# mcu_gateway.net
KiCad netlist of a schematic drawn in Altium Designer
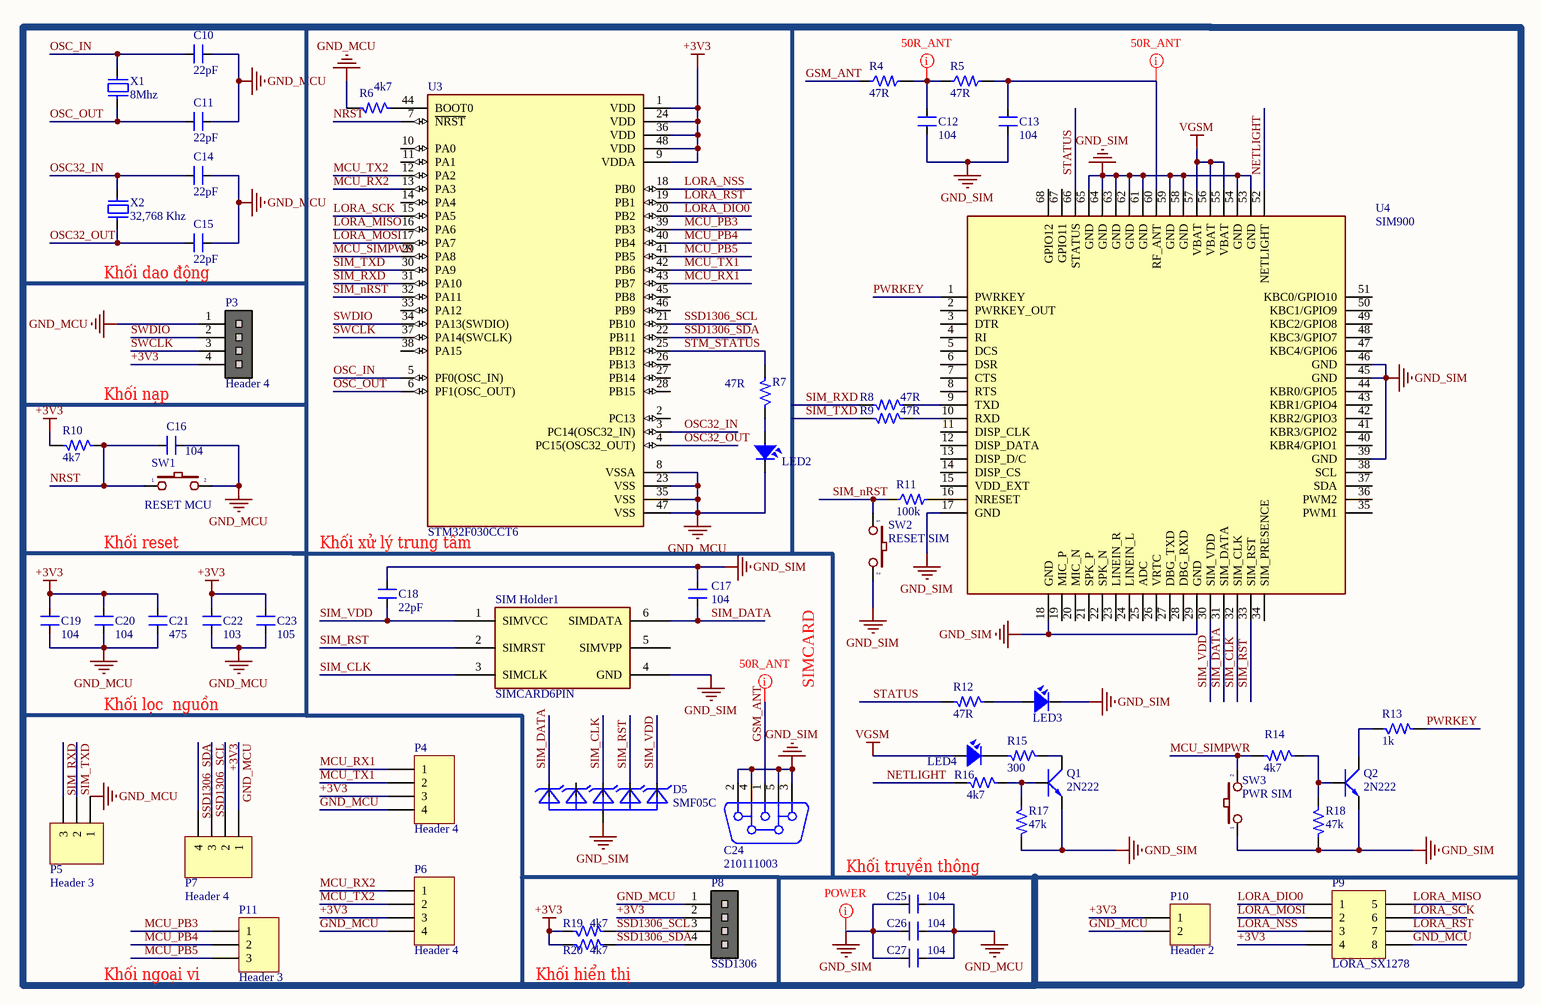
[diagram p0: mcu_gateway.SchDoc]

(export (version "E")
  (design (tool "Eeschema 10.0.6"))
  (components
    (comp (ref "C10")
      (value "22pF")
      (footprint "SM-0805")
      (description "Cap SMD")
      (libsource (lib "syhaunguyen") (part "CM"))
    )
    (comp (ref "C11")
      (value "22pF")
      (footprint "SM-0805")
      (description "Cap SMD")
      (libsource (lib "syhaunguyen") (part "CM"))
    )
    (comp (ref "C12")
      (value "104")
      (footprint "SM-0805")
      (description "Cap SMD")
      (libsource (lib "syhaunguyen") (part "CM"))
    )
    (comp (ref "C13")
      (value "104")
      (footprint "SM-0805")
      (description "Cap SMD")
      (libsource (lib "syhaunguyen") (part "CM"))
    )
    (comp (ref "C14")
      (value "22pF")
      (footprint "SM-0805")
      (description "Cap SMD")
      (libsource (lib "syhaunguyen") (part "CM"))
    )
    (comp (ref "C15")
      (value "22pF")
      (footprint "SM-0805")
      (description "Cap SMD")
      (libsource (lib "syhaunguyen") (part "CM"))
    )
    (comp (ref "C16")
      (value "104")
      (footprint "SM-0805")
      (description "Cap SMD")
      (libsource (lib "syhaunguyen") (part "CM"))
    )
    (comp (ref "C17")
      (value "104")
      (footprint "SM-0805")
      (description "Cap SMD")
      (libsource (lib "syhaunguyen") (part "CM"))
    )
    (comp (ref "C18")
      (value "22pF")
      (footprint "SM-0805")
      (description "Cap SMD")
      (libsource (lib "syhaunguyen") (part "CM"))
    )
    (comp (ref "C19")
      (value "104")
      (footprint "SM-0805")
      (description "Cap SMD")
      (libsource (lib "syhaunguyen") (part "CM"))
    )
    (comp (ref "C20")
      (value "104")
      (footprint "SM-0805")
      (description "Cap SMD")
      (libsource (lib "syhaunguyen") (part "CM"))
    )
    (comp (ref "C21")
      (value "475")
      (footprint "SM-0805")
      (description "Cap SMD")
      (libsource (lib "syhaunguyen") (part "CM"))
    )
    (comp (ref "C22")
      (value "103")
      (footprint "SM-0805")
      (description "Cap SMD")
      (libsource (lib "syhaunguyen") (part "CM"))
    )
    (comp (ref "C23")
      (value "105")
      (footprint "SM-0805")
      (description "Cap SMD")
      (libsource (lib "syhaunguyen") (part "CM"))
    )
    (comp (ref "C24")
      (value "210111003")
      (footprint "SMA-RA")
      (description "CONNECTOR ANTEN")
      (fields
        (field (name "MANUFACTURER") "Würth Elektronik eiSos GmbH")
        (field (name "CREATED BY") "Christin Zierenner")
      )
      (libsource (lib "TechMT.VN_Lib_Project v2") (part "CON Ant"))
    )
    (comp (ref "C25")
      (value "104")
      (footprint "SM-0805")
      (description "Cap SMD")
      (libsource (lib "syhaunguyen") (part "CM"))
    )
    (comp (ref "C26")
      (value "104")
      (footprint "SM-0805")
      (description "Cap SMD")
      (libsource (lib "syhaunguyen") (part "CM"))
    )
    (comp (ref "C27")
      (value "104")
      (footprint "SM-0805")
      (description "Cap SMD")
      (libsource (lib "syhaunguyen") (part "CM"))
    )
    (comp (ref "D5")
      (value "SMF05C")
      (footprint "SC70-6")
      (description "12.5V Clamp 8A _8/20Âµs_ Ipp Tvs Diode Surface Mount SC-88/SC70-6/SOT-363")
      (fields (field (name "MF") "ON Semiconductor"))
      (libsource (lib "SMF05C") (part "SMF05C"))
    )
    (comp (ref "LED2")
      (value "LED")
      (footprint "LED-0805-Green")
      (libsource (lib "TechMT.VN_Lib_Project v2") (part "LED SMD"))
    )
    (comp (ref "LED3")
      (value "LED")
      (footprint "LED-0805-Green")
      (libsource (lib "TechMT.VN_Lib_Project v2") (part "LED SMD"))
    )
    (comp (ref "LED4")
      (value "LED")
      (footprint "LED-0805-Green")
      (libsource (lib "TechMT.VN_Lib_Project v2") (part "LED SMD"))
    )
    (comp (ref "P3")
      (value "Header 4")
      (footprint "HDR 1X4")
      (description "Header, 4-Pin")
      (libsource (lib "Ayric connectors") (part "Header 4"))
    )
    (comp (ref "P4")
      (value "Header 4")
      (footprint "HDR1X4")
      (description "Header, 4-Pin")
      (fields (field (name "PUBLISHER") "Altium Limited"))
      (libsource (lib "") (part "Header 4_1"))
    )
    (comp (ref "P5")
      (value "Header 3")
      (footprint "HDR1X3")
      (description "Header, 3-Pin")
      (fields (field (name "PUBLISHER") "Altium Limited"))
      (libsource (lib "Library AL") (part "Header 3"))
    )
    (comp (ref "P6")
      (value "Header 4")
      (footprint "HDR1X4")
      (description "Header, 4-Pin")
      (fields (field (name "PUBLISHER") "Altium Limited"))
      (libsource (lib "") (part "Header 4_1"))
    )
    (comp (ref "P7")
      (value "Header 4")
      (footprint "HDR1X4")
      (description "Header, 4-Pin")
      (fields (field (name "PUBLISHER") "Altium Limited"))
      (libsource (lib "Library AL") (part "Header 4"))
    )
    (comp (ref "P8")
      (value "SSD1306")
      (footprint "HDR 1X4")
      (description "Header, 4-Pin")
      (libsource (lib "Ayric connectors") (part "Header 4"))
    )
    (comp (ref "P9")
      (value "LORA_SX1278")
      (footprint "HDR2X4_CEN")
      (description "Header, 4-Pin, Dual row")
      (fields (field (name "PUBLISHER") "Altium Limited"))
      (libsource (lib "Library AL") (part "Header 4X2A"))
    )
    (comp (ref "P10")
      (value "Header 2")
      (footprint "HDR1X2")
      (description "Header, 2-Pin")
      (fields (field (name "PUBLISHER") "Altium Limited"))
      (libsource (lib "Library AL") (part "Header 2"))
    )
    (comp (ref "P11")
      (value "Header 3")
      (footprint "HDR1X3")
      (description "Header, 3-Pin")
      (fields (field (name "PUBLISHER") "Altium Limited"))
      (libsource (lib "") (part "Header 3_1"))
    )
    (comp (ref "Q1")
      (value "2N222")
      (footprint "TO92-123")
      (description "NPN 600mW, ECB")
      (fields (field (name "CREAT BY") "MT-TECH.VN"))
      (libsource (lib "TechMT.VN_Lib_Project v2") (part "2N222"))
    )
    (comp (ref "Q2")
      (value "2N222")
      (footprint "TO92-123")
      (description "NPN 600mW, ECB")
      (fields (field (name "CREAT BY") "MT-TECH.VN"))
      (libsource (lib "TechMT.VN_Lib_Project v2") (part "2N222"))
    )
    (comp (ref "R4")
      (value "47R")
      (footprint "R-0805")
      (description "dien tro")
      (libsource (lib "oggy") (part "resistor"))
    )
    (comp (ref "R5")
      (value "47R")
      (footprint "R-0805")
      (description "dien tro")
      (libsource (lib "oggy") (part "resistor"))
    )
    (comp (ref "R6")
      (value "4k7")
      (footprint "R-0805")
      (description "dien tro")
      (libsource (lib "oggy") (part "resistor"))
    )
    (comp (ref "R7")
      (value "47R")
      (footprint "R-0805")
      (description "dien tro")
      (libsource (lib "oggy") (part "resistor"))
    )
    (comp (ref "R8")
      (value "47R")
      (footprint "R-0805")
      (description "dien tro")
      (libsource (lib "oggy") (part "resistor"))
    )
    (comp (ref "R9")
      (value "47R")
      (footprint "R-0805")
      (description "dien tro")
      (libsource (lib "oggy") (part "resistor"))
    )
    (comp (ref "R10")
      (value "4k7")
      (footprint "R-0805")
      (description "dien tro")
      (libsource (lib "oggy") (part "resistor"))
    )
    (comp (ref "R11")
      (value "100k")
      (footprint "R-0805")
      (description "dien tro")
      (libsource (lib "oggy") (part "resistor"))
    )
    (comp (ref "R12")
      (value "47R")
      (footprint "R-0805")
      (description "dien tro")
      (libsource (lib "oggy") (part "resistor"))
    )
    (comp (ref "R13")
      (value "1k")
      (footprint "R-0805")
      (description "dien tro")
      (libsource (lib "oggy") (part "resistor"))
    )
    (comp (ref "R14")
      (value "4k7")
      (footprint "R-0805")
      (description "dien tro")
      (libsource (lib "oggy") (part "resistor"))
    )
    (comp (ref "R15")
      (value "300")
      (footprint "R-0805")
      (description "dien tro")
      (libsource (lib "oggy") (part "resistor"))
    )
    (comp (ref "R16")
      (value "4k7")
      (footprint "R-0805")
      (description "dien tro")
      (libsource (lib "oggy") (part "resistor"))
    )
    (comp (ref "R17")
      (value "47k")
      (footprint "R-0805")
      (description "dien tro")
      (libsource (lib "oggy") (part "resistor"))
    )
    (comp (ref "R18")
      (value "47k")
      (footprint "R-0805")
      (description "dien tro")
      (libsource (lib "oggy") (part "resistor"))
    )
    (comp (ref "R19")
      (value "4k7")
      (footprint "R-0805")
      (description "dien tro")
      (libsource (lib "oggy") (part "resistor"))
    )
    (comp (ref "R20")
      (value "4k7")
      (footprint "R-0805")
      (description "dien tro")
      (libsource (lib "oggy") (part "resistor"))
    )
    (comp (ref "SIM Holder1")
      (value "SIMCARD6PIN")
      (footprint "SIMCARD6pin")
      (libsource (lib "AYRIC Library") (part "SIMCARD6PIN"))
    )
    (comp (ref "SW1")
      (value "RESET MCU")
      (footprint "SW1-SMD")
      (description "Switch button 2 pin")
      (libsource (lib "TechMT.VN_Lib_Project v2") (part "SW2"))
    )
    (comp (ref "SW2")
      (value "RESET SIM")
      (footprint "SW1-SMD")
      (description "Switch button 2 pin")
      (libsource (lib "TechMT.VN_Lib_Project v2") (part "SW2"))
    )
    (comp (ref "SW3")
      (value "PWR SIM")
      (footprint "SW1-SMD")
      (description "Switch button 2 pin")
      (libsource (lib "TechMT.VN_Lib_Project v2") (part "SW2"))
    )
    (comp (ref "U3")
      (value "STM32F030CCT6")
      (footprint "QFP50P900X900X160-48N")
      (description "ARMÂ® CortexÂ®-M0 STM32F0 Microcontroller IC 32-Bit 48MHz 256KB _256K x 8_ FLASH 48-LQFP _7x7_")
      (fields (field (name "MF") "STMicroelectronics") (field (name "DIGI-KEY_PART_NUMBER") "497-17332-2-ND"))
      (libsource (lib "STM32F030CCT6") (part "STM32F030CCT6"))
    )
    (comp (ref "U4") (value "SIM900") (footprint "SIM900") (libsource (lib "AYRIC Library") (part "SIM900")))
    (comp (ref "X1")
      (value "8Mhz")
      (footprint "XT2")
      (description "Crystal For all Crystal 2pin.")
      (libsource (lib "syhaunguyen") (part "XT2"))
    )
    (comp (ref "X2")
      (value "32,768 Khz")
      (footprint "XT32k")
      (description "Crystal 32,768kHz for timer real")
      (libsource (lib "syhaunguyen") (part "XT32k"))
    )
  )
  (nets
    (net (code "1") (name "+3V3") (class "Default")
      (node (ref "C19") (pin "2") (pinfunction "2_2") (pintype "passive"))
      (node (ref "C20") (pin "2") (pinfunction "2_2") (pintype "passive"))
      (node (ref "C21") (pin "2") (pinfunction "2_2") (pintype "passive"))
      (node (ref "C22") (pin "2") (pinfunction "2_2") (pintype "passive"))
      (node (ref "C23") (pin "2") (pinfunction "2_2") (pintype "passive"))
      (node (ref "P10") (pin "1") (pinfunction "1_1") (pintype "passive"))
      (node (ref "P3") (pin "4") (pinfunction "4_4") (pintype "passive"))
      (node (ref "P4") (pin "3") (pinfunction "3_3") (pintype "passive"))
      (node (ref "P6") (pin "3") (pinfunction "3_3") (pintype "passive"))
      (node (ref "P7") (pin "2") (pinfunction "2_2") (pintype "passive"))
      (node (ref "P8") (pin "2") (pinfunction "2_2") (pintype "passive"))
      (node (ref "P9") (pin "4") (pinfunction "4_4") (pintype "passive"))
      (node (ref "R10") (pin "2") (pinfunction "2_2") (pintype "passive"))
      (node (ref "R19") (pin "1") (pinfunction "1_1") (pintype "passive"))
      (node (ref "R20") (pin "1") (pinfunction "1_1") (pintype "passive"))
      (node (ref "U3") (pin "1") (pinfunction "VDD_1") (pintype "power_in"))
      (node (ref "U3") (pin "24") (pinfunction "VDD_24") (pintype "power_in"))
      (node (ref "U3") (pin "36") (pinfunction "VDD_36") (pintype "power_in"))
      (node (ref "U3") (pin "48") (pinfunction "VDD_48") (pintype "power_in"))
      (node (ref "U3") (pin "9") (pinfunction "VDDA_9") (pintype "power_in"))
    )
    (net (code "2") (name "/GSM_ANT") (class "Default")
      (node (ref "C24") (pin "1") (pinfunction "1_1") (pintype "passive"))
      (node (ref "R4") (pin "1") (pinfunction "1_1") (pintype "passive"))
    )
    (net (code "3") (name "/LORA_DIO0") (class "Default")
      (node (ref "P9") (pin "1") (pinfunction "1_1") (pintype "passive"))
      (node (ref "U3") (pin "20") (pinfunction "PB2_20") (pintype "bidirectional"))
    )
    (net (code "4") (name "/LORA_MISO") (class "Default")
      (node (ref "P9") (pin "5") (pinfunction "5_5") (pintype "passive"))
      (node (ref "U3") (pin "16") (pinfunction "PA6_16") (pintype "bidirectional"))
    )
    (net (code "5") (name "/LORA_MOSI") (class "Default")
      (node (ref "P9") (pin "2") (pinfunction "2_2") (pintype "passive"))
      (node (ref "U3") (pin "17") (pinfunction "PA7_17") (pintype "bidirectional"))
    )
    (net (code "6") (name "/LORA_NSS") (class "Default")
      (node (ref "P9") (pin "3") (pinfunction "3_3") (pintype "passive"))
      (node (ref "U3") (pin "18") (pinfunction "PB0_18") (pintype "bidirectional"))
    )
    (net (code "7") (name "/LORA_RST") (class "Default")
      (node (ref "P9") (pin "7") (pinfunction "7_7") (pintype "passive"))
      (node (ref "U3") (pin "19") (pinfunction "PB1_19") (pintype "bidirectional"))
    )
    (net (code "8") (name "/LORA_SCK") (class "Default")
      (node (ref "P9") (pin "6") (pinfunction "6_6") (pintype "passive"))
      (node (ref "U3") (pin "15") (pinfunction "PA5_15") (pintype "bidirectional"))
    )
    (net (code "9") (name "/MCU_PB3") (class "Default")
      (node (ref "P11") (pin "1") (pinfunction "1_1") (pintype "passive"))
      (node (ref "U3") (pin "39") (pinfunction "PB3_39") (pintype "bidirectional"))
    )
    (net (code "10") (name "/MCU_PB4") (class "Default")
      (node (ref "P11") (pin "2") (pinfunction "2_2") (pintype "passive"))
      (node (ref "U3") (pin "40") (pinfunction "PB4_40") (pintype "bidirectional"))
    )
    (net (code "11") (name "/MCU_PB5") (class "Default")
      (node (ref "P11") (pin "3") (pinfunction "3_3") (pintype "passive"))
      (node (ref "U3") (pin "41") (pinfunction "PB5_41") (pintype "bidirectional"))
    )
    (net (code "12") (name "/MCU_RX1") (class "Default")
      (node (ref "P4") (pin "1") (pinfunction "1_1") (pintype "passive"))
      (node (ref "U3") (pin "43") (pinfunction "PB7_43") (pintype "bidirectional"))
    )
    (net (code "13") (name "/MCU_RX2") (class "Default")
      (node (ref "P6") (pin "1") (pinfunction "1_1") (pintype "passive"))
      (node (ref "U3") (pin "13") (pinfunction "PA3_13") (pintype "bidirectional"))
    )
    (net (code "14") (name "/MCU_SIMPWR") (class "Default")
      (node (ref "R14") (pin "2") (pinfunction "2_2") (pintype "passive"))
      (node (ref "SW3") (pin "2") (pinfunction "2_2") (pintype "passive"))
      (node (ref "U3") (pin "29") (pinfunction "PA8_29") (pintype "bidirectional"))
    )
    (net (code "15") (name "/MCU_TX1") (class "Default")
      (node (ref "P4") (pin "2") (pinfunction "2_2") (pintype "passive"))
      (node (ref "U3") (pin "42") (pinfunction "PB6_42") (pintype "bidirectional"))
    )
    (net (code "16") (name "/MCU_TX2") (class "Default")
      (node (ref "P6") (pin "2") (pinfunction "2_2") (pintype "passive"))
      (node (ref "U3") (pin "12") (pinfunction "PA2_12") (pintype "bidirectional"))
    )
    (net (code "17") (name "/NETLIGHT") (class "Default")
      (node (ref "R16") (pin "2") (pinfunction "2_2") (pintype "passive"))
      (node (ref "U4") (pin "52") (pinfunction "NETLIGHT_52") (pintype "passive"))
    )
    (net (code "18") (name "/NRST") (class "Default")
      (node (ref "C16") (pin "1") (pinfunction "1_1") (pintype "passive"))
      (node (ref "R10") (pin "1") (pinfunction "1_1") (pintype "passive"))
      (node (ref "SW1") (pin "1") (pinfunction "1_1") (pintype "passive"))
      (node (ref "U3") (pin "7") (pinfunction "~{NRST}_7") (pintype "bidirectional"))
    )
    (net (code "19") (name "/OSC32_IN") (class "Default")
      (node (ref "C14") (pin "2") (pinfunction "2_2") (pintype "passive"))
      (node (ref "U3") (pin "3") (pinfunction "PC14(OSC32_IN)_3") (pintype "bidirectional"))
      (node (ref "X2") (pin "2") (pinfunction "2_2") (pintype "passive"))
    )
    (net (code "20") (name "/OSC32_OUT") (class "Default")
      (node (ref "C15") (pin "2") (pinfunction "2_2") (pintype "passive"))
      (node (ref "U3") (pin "4") (pinfunction "PC15(OSC32_OUT)_4") (pintype "bidirectional"))
      (node (ref "X2") (pin "1") (pinfunction "1_1") (pintype "passive"))
    )
    (net (code "21") (name "/OSC_IN") (class "Default")
      (node (ref "C10") (pin "2") (pinfunction "2_2") (pintype "passive"))
      (node (ref "U3") (pin "5") (pinfunction "PF0(OSC_IN)_5") (pintype "bidirectional"))
      (node (ref "X1") (pin "2") (pinfunction "2_2") (pintype "passive"))
    )
    (net (code "22") (name "/OSC_OUT") (class "Default")
      (node (ref "C11") (pin "2") (pinfunction "2_2") (pintype "passive"))
      (node (ref "U3") (pin "6") (pinfunction "PF1(OSC_OUT)_6") (pintype "bidirectional"))
      (node (ref "X1") (pin "1") (pinfunction "1_1") (pintype "passive"))
    )
    (net (code "23") (name "/PWRKEY") (class "Default")
      (node (ref "R13") (pin "2") (pinfunction "2_2") (pintype "passive"))
      (node (ref "U4") (pin "1") (pinfunction "PWRKEY_1") (pintype "passive"))
    )
    (net (code "24") (name "/SIM_CLK") (class "Default")
      (node (ref "D5") (pin "4") (pinfunction "C3_4") (pintype "passive"))
      (node (ref "SIM Holder1") (pin "3") (pinfunction "SIMCLK_3") (pintype "passive"))
      (node (ref "U4") (pin "32") (pinfunction "SIM_CLK_32") (pintype "passive"))
    )
    (net (code "25") (name "/SIM_DATA") (class "Default")
      (node (ref "C17") (pin "1") (pinfunction "1_1") (pintype "passive"))
      (node (ref "D5") (pin "1") (pinfunction "C1_1") (pintype "passive"))
      (node (ref "SIM Holder1") (pin "6") (pinfunction "SIMDATA_6") (pintype "passive"))
      (node (ref "U4") (pin "31") (pinfunction "SIM_DATA_31") (pintype "passive"))
    )
    (net (code "26") (name "/SIM_RST") (class "Default")
      (node (ref "D5") (pin "5") (pinfunction "C4_5") (pintype "passive"))
      (node (ref "SIM Holder1") (pin "2") (pinfunction "SIMRST_2") (pintype "passive"))
      (node (ref "U4") (pin "33") (pinfunction "SIM_RST_33") (pintype "passive"))
    )
    (net (code "27") (name "/SIM_RXD") (class "Default")
      (node (ref "P5") (pin "3") (pinfunction "3_3") (pintype "passive"))
      (node (ref "R8") (pin "2") (pinfunction "2_2") (pintype "passive"))
      (node (ref "U3") (pin "31") (pinfunction "PA10_31") (pintype "bidirectional"))
    )
    (net (code "28") (name "/SIM_TXD") (class "Default")
      (node (ref "P5") (pin "2") (pinfunction "2_2") (pintype "passive"))
      (node (ref "R9") (pin "2") (pinfunction "2_2") (pintype "passive"))
      (node (ref "U3") (pin "30") (pinfunction "PA9_30") (pintype "bidirectional"))
    )
    (net (code "29") (name "/SIM_VDD") (class "Default")
      (node (ref "C18") (pin "1") (pinfunction "1_1") (pintype "passive"))
      (node (ref "D5") (pin "6") (pinfunction "C5_6") (pintype "passive"))
      (node (ref "SIM Holder1") (pin "1") (pinfunction "SIMVCC_1") (pintype "passive"))
      (node (ref "U4") (pin "30") (pinfunction "SIM_VDD_30") (pintype "passive"))
    )
    (net (code "30") (name "/SIM_nRST") (class "Default")
      (node (ref "R11") (pin "1") (pinfunction "1_1") (pintype "passive"))
      (node (ref "SW2") (pin "1") (pinfunction "1_1") (pintype "passive"))
      (node (ref "U3") (pin "32") (pinfunction "PA11_32") (pintype "bidirectional"))
    )
    (net (code "31") (name "/SSD1306_SCL") (class "Default")
      (node (ref "P7") (pin "3") (pinfunction "3_3") (pintype "passive"))
      (node (ref "P8") (pin "3") (pinfunction "3_3") (pintype "passive"))
      (node (ref "R19") (pin "2") (pinfunction "2_2") (pintype "passive"))
      (node (ref "U3") (pin "21") (pinfunction "PB10_21") (pintype "bidirectional"))
    )
    (net (code "32") (name "/SSD1306_SDA") (class "Default")
      (node (ref "P7") (pin "4") (pinfunction "4_4") (pintype "passive"))
      (node (ref "P8") (pin "4") (pinfunction "4_4") (pintype "passive"))
      (node (ref "R20") (pin "2") (pinfunction "2_2") (pintype "passive"))
      (node (ref "U3") (pin "22") (pinfunction "PB11_22") (pintype "bidirectional"))
    )
    (net (code "33") (name "/STATUS") (class "Default")
      (node (ref "R12") (pin "2") (pinfunction "2_2") (pintype "passive"))
      (node (ref "U4") (pin "66") (pinfunction "STATUS_66") (pintype "passive"))
    )
    (net (code "34") (name "/STM_STATUS") (class "Default")
      (node (ref "R7") (pin "2") (pinfunction "2_2") (pintype "passive"))
      (node (ref "U3") (pin "25") (pinfunction "PB12_25") (pintype "bidirectional"))
    )
    (net (code "35") (name "/SWCLK") (class "Default")
      (node (ref "P3") (pin "3") (pinfunction "3_3") (pintype "passive"))
      (node (ref "U3") (pin "37") (pinfunction "PA14(SWCLK)_37") (pintype "bidirectional"))
    )
    (net (code "36") (name "/SWDIO") (class "Default")
      (node (ref "P3") (pin "2") (pinfunction "2_2") (pintype "passive"))
      (node (ref "U3") (pin "34") (pinfunction "PA13(SWDIO)_34") (pintype "bidirectional"))
    )
    (net (code "37") (name "GND_MCU") (class "Default")
      (node (ref "C10") (pin "1") (pinfunction "1_1") (pintype "passive"))
      (node (ref "C11") (pin "1") (pinfunction "1_1") (pintype "passive"))
      (node (ref "C14") (pin "1") (pinfunction "1_1") (pintype "passive"))
      (node (ref "C15") (pin "1") (pinfunction "1_1") (pintype "passive"))
      (node (ref "C16") (pin "2") (pinfunction "2_2") (pintype "passive"))
      (node (ref "C19") (pin "1") (pinfunction "1_1") (pintype "passive"))
      (node (ref "C20") (pin "1") (pinfunction "1_1") (pintype "passive"))
      (node (ref "C21") (pin "1") (pinfunction "1_1") (pintype "passive"))
      (node (ref "C22") (pin "1") (pinfunction "1_1") (pintype "passive"))
      (node (ref "C23") (pin "1") (pinfunction "1_1") (pintype "passive"))
      (node (ref "C25") (pin "2") (pinfunction "2_2") (pintype "passive"))
      (node (ref "C26") (pin "2") (pinfunction "2_2") (pintype "passive"))
      (node (ref "C27") (pin "2") (pinfunction "2_2") (pintype "passive"))
      (node (ref "LED2") (pin "2") (pinfunction "2_2") (pintype "passive"))
      (node (ref "P10") (pin "2") (pinfunction "2_2") (pintype "passive"))
      (node (ref "P3") (pin "1") (pinfunction "1_1") (pintype "passive"))
      (node (ref "P4") (pin "4") (pinfunction "4_4") (pintype "passive"))
      (node (ref "P5") (pin "1") (pinfunction "1_1") (pintype "passive"))
      (node (ref "P6") (pin "4") (pinfunction "4_4") (pintype "passive"))
      (node (ref "P7") (pin "1") (pinfunction "1_1") (pintype "passive"))
      (node (ref "P8") (pin "1") (pinfunction "1_1") (pintype "passive"))
      (node (ref "P9") (pin "8") (pinfunction "8_8") (pintype "passive"))
      (node (ref "R6") (pin "2") (pinfunction "2_2") (pintype "passive"))
      (node (ref "SW1") (pin "2") (pinfunction "2_2") (pintype "passive"))
      (node (ref "U3") (pin "23") (pinfunction "VSS_23") (pintype "power_in"))
      (node (ref "U3") (pin "35") (pinfunction "VSS_35") (pintype "power_in"))
      (node (ref "U3") (pin "47") (pinfunction "VSS_47") (pintype "power_in"))
      (node (ref "U3") (pin "8") (pinfunction "VSSA_8") (pintype "power_in"))
    )
    (net (code "38") (name "GND_SIM") (class "Default")
      (node (ref "C12") (pin "1") (pinfunction "1_1") (pintype "passive"))
      (node (ref "C13") (pin "1") (pinfunction "1_1") (pintype "passive"))
      (node (ref "C17") (pin "2") (pinfunction "2_2") (pintype "passive"))
      (node (ref "C18") (pin "2") (pinfunction "2_2") (pintype "passive"))
      (node (ref "C24") (pin "2") (pinfunction "2_2") (pintype "passive"))
      (node (ref "C24") (pin "3") (pinfunction "3_3") (pintype "passive"))
      (node (ref "C24") (pin "4") (pinfunction "4_4") (pintype "passive"))
      (node (ref "C24") (pin "5") (pinfunction "5_5") (pintype "passive"))
      (node (ref "C25") (pin "1") (pinfunction "1_1") (pintype "passive"))
      (node (ref "C26") (pin "1") (pinfunction "1_1") (pintype "passive"))
      (node (ref "C27") (pin "1") (pinfunction "1_1") (pintype "passive"))
      (node (ref "D5") (pin "2") (pinfunction "A_2") (pintype "passive"))
      (node (ref "LED3") (pin "2") (pinfunction "2_2") (pintype "passive"))
      (node (ref "Q1") (pin "1") (pinfunction "E_1") (pintype "passive"))
      (node (ref "Q2") (pin "1") (pinfunction "E_1") (pintype "passive"))
      (node (ref "R17") (pin "2") (pinfunction "2_2") (pintype "passive"))
      (node (ref "R18") (pin "2") (pinfunction "2_2") (pintype "passive"))
      (node (ref "SIM Holder1") (pin "4") (pinfunction "GND_4") (pintype "passive"))
      (node (ref "SW2") (pin "2") (pinfunction "2_2") (pintype "passive"))
      (node (ref "SW3") (pin "1") (pinfunction "1_1") (pintype "passive"))
      (node (ref "U4") (pin "17") (pinfunction "GND_17") (pintype "passive"))
      (node (ref "U4") (pin "18") (pinfunction "GND_18") (pintype "passive"))
      (node (ref "U4") (pin "29") (pinfunction "GND_29") (pintype "passive"))
      (node (ref "U4") (pin "39") (pinfunction "GND_39") (pintype "passive"))
      (node (ref "U4") (pin "45") (pinfunction "GND_45") (pintype "passive"))
      (node (ref "U4") (pin "46") (pinfunction "GND_46") (pintype "passive"))
      (node (ref "U4") (pin "53") (pinfunction "GND_53") (pintype "passive"))
      (node (ref "U4") (pin "54") (pinfunction "GND_54") (pintype "passive"))
      (node (ref "U4") (pin "58") (pinfunction "GND_58") (pintype "passive"))
      (node (ref "U4") (pin "59") (pinfunction "GND_59") (pintype "passive"))
      (node (ref "U4") (pin "61") (pinfunction "GND_61") (pintype "passive"))
      (node (ref "U4") (pin "62") (pinfunction "GND_62") (pintype "passive"))
      (node (ref "U4") (pin "63") (pinfunction "GND_63") (pintype "passive"))
      (node (ref "U4") (pin "64") (pinfunction "GND_64") (pintype "passive"))
      (node (ref "U4") (pin "65") (pinfunction "GND_65") (pintype "passive"))
    )
    (net (code "39") (name "Net-(C12-Pad2)") (class "Default")
      (node (ref "C12") (pin "2") (pinfunction "2_2") (pintype "passive"))
      (node (ref "R4") (pin "2") (pinfunction "2_2") (pintype "passive"))
      (node (ref "R5") (pin "1") (pinfunction "1_1") (pintype "passive"))
    )
    (net (code "40") (name "Net-(LED2-Pad1)") (class "Default")
      (node (ref "LED2") (pin "1") (pinfunction "1_1") (pintype "passive"))
      (node (ref "R7") (pin "1") (pinfunction "1_1") (pintype "passive"))
    )
    (net (code "41") (name "Net-(LED3-Pad1)") (class "Default")
      (node (ref "LED3") (pin "1") (pinfunction "1_1") (pintype "passive"))
      (node (ref "R12") (pin "1") (pinfunction "1_1") (pintype "passive"))
    )
    (net (code "42") (name "Net-(LED4-Pad2)") (class "Default")
      (node (ref "LED4") (pin "2") (pinfunction "2_2") (pintype "passive"))
      (node (ref "R15") (pin "2") (pinfunction "2_2") (pintype "passive"))
    )
    (net (code "43") (name "Net-(Q1-B)") (class "Default")
      (node (ref "Q1") (pin "2") (pinfunction "B_2") (pintype "passive"))
      (node (ref "R16") (pin "1") (pinfunction "1_1") (pintype "passive"))
      (node (ref "R17") (pin "1") (pinfunction "1_1") (pintype "passive"))
    )
    (net (code "44") (name "Net-(Q1-C)") (class "Default")
      (node (ref "Q1") (pin "3") (pinfunction "C_3") (pintype "passive"))
      (node (ref "R15") (pin "1") (pinfunction "1_1") (pintype "passive"))
    )
    (net (code "45") (name "Net-(Q2-B)") (class "Default")
      (node (ref "Q2") (pin "2") (pinfunction "B_2") (pintype "passive"))
      (node (ref "R14") (pin "1") (pinfunction "1_1") (pintype "passive"))
      (node (ref "R18") (pin "1") (pinfunction "1_1") (pintype "passive"))
    )
    (net (code "46") (name "Net-(Q2-C)") (class "Default")
      (node (ref "Q2") (pin "3") (pinfunction "C_3") (pintype "passive"))
      (node (ref "R13") (pin "1") (pinfunction "1_1") (pintype "passive"))
    )
    (net (code "47") (name "Net-(U3-BOOT0)") (class "Default")
      (node (ref "R6") (pin "1") (pinfunction "1_1") (pintype "passive"))
      (node (ref "U3") (pin "44") (pinfunction "BOOT0_44") (pintype "passive"))
    )
    (net (code "48") (name "Net-(U4-NRESET)") (class "Default")
      (node (ref "R11") (pin "2") (pinfunction "2_2") (pintype "passive"))
      (node (ref "U4") (pin "16") (pinfunction "NRESET_16") (pintype "passive"))
    )
    (net (code "49") (name "Net-(U4-RF_ANT)") (class "Default")
      (node (ref "C13") (pin "2") (pinfunction "2_2") (pintype "passive"))
      (node (ref "R5") (pin "2") (pinfunction "2_2") (pintype "passive"))
      (node (ref "U4") (pin "60") (pinfunction "RF_ANT_60") (pintype "passive"))
    )
    (net (code "50") (name "Net-(U4-RXD)") (class "Default")
      (node (ref "R9") (pin "1") (pinfunction "1_1") (pintype "passive"))
      (node (ref "U4") (pin "10") (pinfunction "RXD_10") (pintype "passive"))
    )
    (net (code "51") (name "Net-(U4-TXD)") (class "Default")
      (node (ref "R8") (pin "1") (pinfunction "1_1") (pintype "passive"))
      (node (ref "U4") (pin "9") (pinfunction "TXD_9") (pintype "passive"))
    )
    (net (code "52") (name "VGSM") (class "Default")
      (node (ref "LED4") (pin "1") (pinfunction "1_1") (pintype "passive"))
      (node (ref "U4") (pin "55") (pinfunction "VBAT_55") (pintype "passive"))
      (node (ref "U4") (pin "56") (pinfunction "VBAT_56") (pintype "passive"))
      (node (ref "U4") (pin "57") (pinfunction "VBAT_57") (pintype "passive"))
    )
    (net (code "53") (name "unconnected-(D5-C2-Pad3)") (class "Default")
      (node (ref "D5") (pin "3") (pinfunction "C2_3") (pintype "passive"))
    )
    (net (code "54") (name "unconnected-(SIM Holder1-SIMVPP-Pad5)") (class "Default")
      (node (ref "SIM Holder1") (pin "5") (pinfunction "SIMVPP_5") (pintype "passive"))
    )
    (net (code "55") (name "unconnected-(U3-PA0-Pad10)") (class "Default")
      (node (ref "U3") (pin "10") (pinfunction "PA0_10") (pintype "bidirectional"))
    )
    (net (code "56") (name "unconnected-(U3-PA1-Pad11)") (class "Default")
      (node (ref "U3") (pin "11") (pinfunction "PA1_11") (pintype "bidirectional"))
    )
    (net (code "57") (name "unconnected-(U3-PA4-Pad14)") (class "Default")
      (node (ref "U3") (pin "14") (pinfunction "PA4_14") (pintype "bidirectional"))
    )
    (net (code "58") (name "unconnected-(U3-PA12-Pad33)") (class "Default")
      (node (ref "U3") (pin "33") (pinfunction "PA12_33") (pintype "bidirectional"))
    )
    (net (code "59") (name "unconnected-(U3-PA15-Pad38)") (class "Default")
      (node (ref "U3") (pin "38") (pinfunction "PA15_38") (pintype "bidirectional"))
    )
    (net (code "60") (name "unconnected-(U3-PB8-Pad45)") (class "Default")
      (node (ref "U3") (pin "45") (pinfunction "PB8_45") (pintype "bidirectional"))
    )
    (net (code "61") (name "unconnected-(U3-PB9-Pad46)") (class "Default")
      (node (ref "U3") (pin "46") (pinfunction "PB9_46") (pintype "bidirectional"))
    )
    (net (code "62") (name "unconnected-(U3-PB13-Pad26)") (class "Default")
      (node (ref "U3") (pin "26") (pinfunction "PB13_26") (pintype "bidirectional"))
    )
    (net (code "63") (name "unconnected-(U3-PB14-Pad27)") (class "Default")
      (node (ref "U3") (pin "27") (pinfunction "PB14_27") (pintype "bidirectional"))
    )
    (net (code "64") (name "unconnected-(U3-PB15-Pad28)") (class "Default")
      (node (ref "U3") (pin "28") (pinfunction "PB15_28") (pintype "bidirectional"))
    )
    (net (code "65") (name "unconnected-(U3-PC13-Pad2)") (class "Default")
      (node (ref "U3") (pin "2") (pinfunction "PC13_2") (pintype "bidirectional"))
    )
    (net (code "66") (name "unconnected-(U4-ADC-Pad25)") (class "Default")
      (node (ref "U4") (pin "25") (pinfunction "ADC_25") (pintype "passive"))
    )
    (net (code "67") (name "unconnected-(U4-CTS-Pad7)") (class "Default")
      (node (ref "U4") (pin "7") (pinfunction "CTS_7") (pintype "passive"))
    )
    (net (code "68") (name "unconnected-(U4-DBG_RXD-Pad28)") (class "Default")
      (node (ref "U4") (pin "28") (pinfunction "DBG_RXD_28") (pintype "passive"))
    )
    (net (code "69") (name "unconnected-(U4-DBG_TXD-Pad27)") (class "Default")
      (node (ref "U4") (pin "27") (pinfunction "DBG_TXD_27") (pintype "passive"))
    )
    (net (code "70") (name "unconnected-(U4-DCS-Pad5)") (class "Default")
      (node (ref "U4") (pin "5") (pinfunction "DCS_5") (pintype "passive"))
    )
    (net (code "71") (name "unconnected-(U4-DISP_CLK-Pad11)") (class "Default")
      (node (ref "U4") (pin "11") (pinfunction "DISP_CLK_11") (pintype "passive"))
    )
    (net (code "72") (name "unconnected-(U4-DISP_CS-Pad14)") (class "Default")
      (node (ref "U4") (pin "14") (pinfunction "DISP_CS_14") (pintype "passive"))
    )
    (net (code "73") (name "unconnected-(U4-DISP_DATA-Pad12)") (class "Default")
      (node (ref "U4") (pin "12") (pinfunction "DISP_DATA_12") (pintype "passive"))
    )
    (net (code "74") (name "unconnected-(U4-DISP_D{slash}C-Pad13)") (class "Default")
      (node (ref "U4") (pin "13") (pinfunction "DISP_D/C_13") (pintype "passive"))
    )
    (net (code "75") (name "unconnected-(U4-DSR-Pad6)") (class "Default")
      (node (ref "U4") (pin "6") (pinfunction "DSR_6") (pintype "passive"))
    )
    (net (code "76") (name "unconnected-(U4-DTR-Pad3)") (class "Default")
      (node (ref "U4") (pin "3") (pinfunction "DTR_3") (pintype "passive"))
    )
    (net (code "77") (name "unconnected-(U4-GPIO11-Pad67)") (class "Default")
      (node (ref "U4") (pin "67") (pinfunction "GPIO11_67") (pintype "passive"))
    )
    (net (code "78") (name "unconnected-(U4-GPIO12-Pad68)") (class "Default")
      (node (ref "U4") (pin "68") (pinfunction "GPIO12_68") (pintype "passive"))
    )
    (net (code "79") (name "unconnected-(U4-KBC0{slash}GPIO10-Pad51)") (class "Default")
      (node (ref "U4") (pin "51") (pinfunction "KBC0/GPIO10_51") (pintype "passive"))
    )
    (net (code "80") (name "unconnected-(U4-KBC1{slash}GPIO9-Pad50)") (class "Default")
      (node (ref "U4") (pin "50") (pinfunction "KBC1/GPIO9_50") (pintype "passive"))
    )
    (net (code "81") (name "unconnected-(U4-KBC2{slash}GPIO8-Pad49)") (class "Default")
      (node (ref "U4") (pin "49") (pinfunction "KBC2/GPIO8_49") (pintype "passive"))
    )
    (net (code "82") (name "unconnected-(U4-KBC3{slash}GPIO7-Pad48)") (class "Default")
      (node (ref "U4") (pin "48") (pinfunction "KBC3/GPIO7_48") (pintype "passive"))
    )
    (net (code "83") (name "unconnected-(U4-KBC4{slash}GPIO6-Pad47)") (class "Default")
      (node (ref "U4") (pin "47") (pinfunction "KBC4/GPIO6_47") (pintype "passive"))
    )
    (net (code "84") (name "unconnected-(U4-KBR0{slash}GPIO5-Pad44)") (class "Default")
      (node (ref "U4") (pin "44") (pinfunction "KBR0/GPIO5_44") (pintype "passive"))
    )
    (net (code "85") (name "unconnected-(U4-KBR1{slash}GPIO4-Pad43)") (class "Default")
      (node (ref "U4") (pin "43") (pinfunction "KBR1/GPIO4_43") (pintype "passive"))
    )
    (net (code "86") (name "unconnected-(U4-KBR2{slash}GPIO3-Pad42)") (class "Default")
      (node (ref "U4") (pin "42") (pinfunction "KBR2/GPIO3_42") (pintype "passive"))
    )
    (net (code "87") (name "unconnected-(U4-KBR3{slash}GPIO2-Pad41)") (class "Default")
      (node (ref "U4") (pin "41") (pinfunction "KBR3/GPIO2_41") (pintype "passive"))
    )
    (net (code "88") (name "unconnected-(U4-KBR4{slash}GPIO1-Pad40)") (class "Default")
      (node (ref "U4") (pin "40") (pinfunction "KBR4/GPIO1_40") (pintype "passive"))
    )
    (net (code "89") (name "unconnected-(U4-LINEIN_L-Pad24)") (class "Default")
      (node (ref "U4") (pin "24") (pinfunction "LINEIN_L_24") (pintype "passive"))
    )
    (net (code "90") (name "unconnected-(U4-LINEIN_R-Pad23)") (class "Default")
      (node (ref "U4") (pin "23") (pinfunction "LINEIN_R_23") (pintype "passive"))
    )
    (net (code "91") (name "unconnected-(U4-MIC_N-Pad20)") (class "Default")
      (node (ref "U4") (pin "20") (pinfunction "MIC_N_20") (pintype "passive"))
    )
    (net (code "92") (name "unconnected-(U4-MIC_P-Pad19)") (class "Default")
      (node (ref "U4") (pin "19") (pinfunction "MIC_P_19") (pintype "passive"))
    )
    (net (code "93") (name "unconnected-(U4-PWM1-Pad35)") (class "Default")
      (node (ref "U4") (pin "35") (pinfunction "PWM1_35") (pintype "passive"))
    )
    (net (code "94") (name "unconnected-(U4-PWM2-Pad36)") (class "Default")
      (node (ref "U4") (pin "36") (pinfunction "PWM2_36") (pintype "passive"))
    )
    (net (code "95") (name "unconnected-(U4-PWRKEY_OUT-Pad2)") (class "Default")
      (node (ref "U4") (pin "2") (pinfunction "PWRKEY_OUT_2") (pintype "passive"))
    )
    (net (code "96") (name "unconnected-(U4-RI-Pad4)") (class "Default")
      (node (ref "U4") (pin "4") (pinfunction "RI_4") (pintype "passive"))
    )
    (net (code "97") (name "unconnected-(U4-RTS-Pad8)") (class "Default")
      (node (ref "U4") (pin "8") (pinfunction "RTS_8") (pintype "passive"))
    )
    (net (code "98") (name "unconnected-(U4-SCL-Pad38)") (class "Default")
      (node (ref "U4") (pin "38") (pinfunction "SCL_38") (pintype "passive"))
    )
    (net (code "99") (name "unconnected-(U4-SDA-Pad37)") (class "Default")
      (node (ref "U4") (pin "37") (pinfunction "SDA_37") (pintype "passive"))
    )
    (net (code "100") (name "unconnected-(U4-SIM_PRESENCE-Pad34)") (class "Default")
      (node (ref "U4") (pin "34") (pinfunction "SIM_PRESENCE_34") (pintype "passive"))
    )
    (net (code "101") (name "unconnected-(U4-SPK_N-Pad22)") (class "Default")
      (node (ref "U4") (pin "22") (pinfunction "SPK_N_22") (pintype "passive"))
    )
    (net (code "102") (name "unconnected-(U4-SPK_P-Pad21)") (class "Default")
      (node (ref "U4") (pin "21") (pinfunction "SPK_P_21") (pintype "passive"))
    )
    (net (code "103") (name "unconnected-(U4-VDD_EXT-Pad15)") (class "Default")
      (node (ref "U4") (pin "15") (pinfunction "VDD_EXT_15") (pintype "passive"))
    )
    (net (code "104") (name "unconnected-(U4-VRTC-Pad26)") (class "Default")
      (node (ref "U4") (pin "26") (pinfunction "VRTC_26") (pintype "passive"))
    )
  )
)
